# Ctrl_Btnrgb_brd.net
KiCad netlist of a schematic drawn in EAGLE
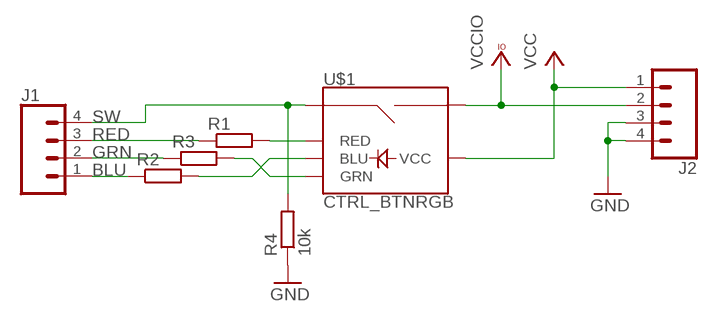
[diagram p0: schematic, sheet 1]

(export (version "E")
  (design (tool "Eeschema 10.0.6"))
  (components
    (comp (ref "J1")
      (value "CONN_04")
      (footprint "eagle-import:1X04")
      (libsource (lib "eagle-import") (part "CONN_04"))
    )
    (comp (ref "J2")
      (value "CONN_04")
      (footprint "eagle-import:1X04")
      (libsource (lib "eagle-import") (part "CONN_04"))
    )
    (comp (ref "R1")
      (value "R-EU_R0603")
      (footprint "eagle-import:R0603")
      (libsource (lib "eagle-import") (part "R-EU_R0603"))
    )
    (comp (ref "R2")
      (value "R-EU_R0603")
      (footprint "eagle-import:R0603")
      (libsource (lib "eagle-import") (part "R-EU_R0603"))
    )
    (comp (ref "R3")
      (value "R-EU_R0603")
      (footprint "eagle-import:R0603")
      (libsource (lib "eagle-import") (part "R-EU_R0603"))
    )
    (comp (ref "R4")
      (value "10k")
      (footprint "eagle-import:R0603")
      (libsource (lib "eagle-import") (part "R-EU_R0603"))
    )
    (comp (ref "U$1")
      (value "CTRL_BTNRGB")
      (footprint "eagle-import:CTRL_BTNRGB")
      (libsource (lib "eagle-import") (part "CTRL_BTNRGB"))
    )
  )
  (nets
    (net (code "1") (name "/BLU") (class "Default")
      (node (ref "J1") (pin "1") (pinfunction "1_1") (pintype "passive"))
      (node (ref "R2") (pin "1") (pinfunction "1_1") (pintype "passive"))
    )
    (net (code "2") (name "/GRN") (class "Default")
      (node (ref "J1") (pin "2") (pinfunction "2_2") (pintype "passive"))
      (node (ref "R3") (pin "1") (pinfunction "1_1") (pintype "passive"))
    )
    (net (code "3") (name "/RED") (class "Default")
      (node (ref "J1") (pin "3") (pinfunction "3_3") (pintype "passive"))
      (node (ref "R1") (pin "1") (pinfunction "1_1") (pintype "passive"))
    )
    (net (code "4") (name "/SW") (class "Default")
      (node (ref "J1") (pin "4") (pinfunction "4_4") (pintype "passive"))
      (node (ref "R4") (pin "2") (pinfunction "2_2") (pintype "passive"))
      (node (ref "U$1") (pin "SIG1") (pinfunction "SIG1_SIG1") (pintype "bidirectional"))
    )
    (net (code "5") (name "GND") (class "Default")
      (node (ref "J2") (pin "3") (pinfunction "3_3") (pintype "passive"))
      (node (ref "J2") (pin "4") (pinfunction "4_4") (pintype "passive"))
      (node (ref "R4") (pin "1") (pinfunction "1_1") (pintype "passive"))
    )
    (net (code "6") (name "Net-(R1-Pad2)") (class "Default")
      (node (ref "R1") (pin "2") (pinfunction "2_2") (pintype "passive"))
      (node (ref "U$1") (pin "RED") (pinfunction "RED_RED") (pintype "bidirectional"))
    )
    (net (code "7") (name "Net-(R2-Pad2)") (class "Default")
      (node (ref "R2") (pin "2") (pinfunction "2_2") (pintype "passive"))
      (node (ref "U$1") (pin "BLU") (pinfunction "BLU_BLU") (pintype "bidirectional"))
    )
    (net (code "8") (name "Net-(R3-Pad2)") (class "Default")
      (node (ref "R3") (pin "2") (pinfunction "2_2") (pintype "passive"))
      (node (ref "U$1") (pin "GRN") (pinfunction "GRN_GRN") (pintype "bidirectional"))
    )
    (net (code "9") (name "VCC") (class "Default")
      (node (ref "J2") (pin "1") (pinfunction "1_1") (pintype "passive"))
      (node (ref "U$1") (pin "VCC") (pinfunction "VCC_VCC") (pintype "bidirectional"))
    )
    (net (code "10") (name "VCCIO") (class "Default")
      (node (ref "J2") (pin "2") (pinfunction "2_2") (pintype "passive"))
      (node (ref "U$1") (pin "SIG2") (pinfunction "SIG2_SIG2") (pintype "bidirectional"))
    )
  )
)
